# RILey-PCB_V2_0_v57.net
KiCad netlist of a schematic drawn in EAGLE
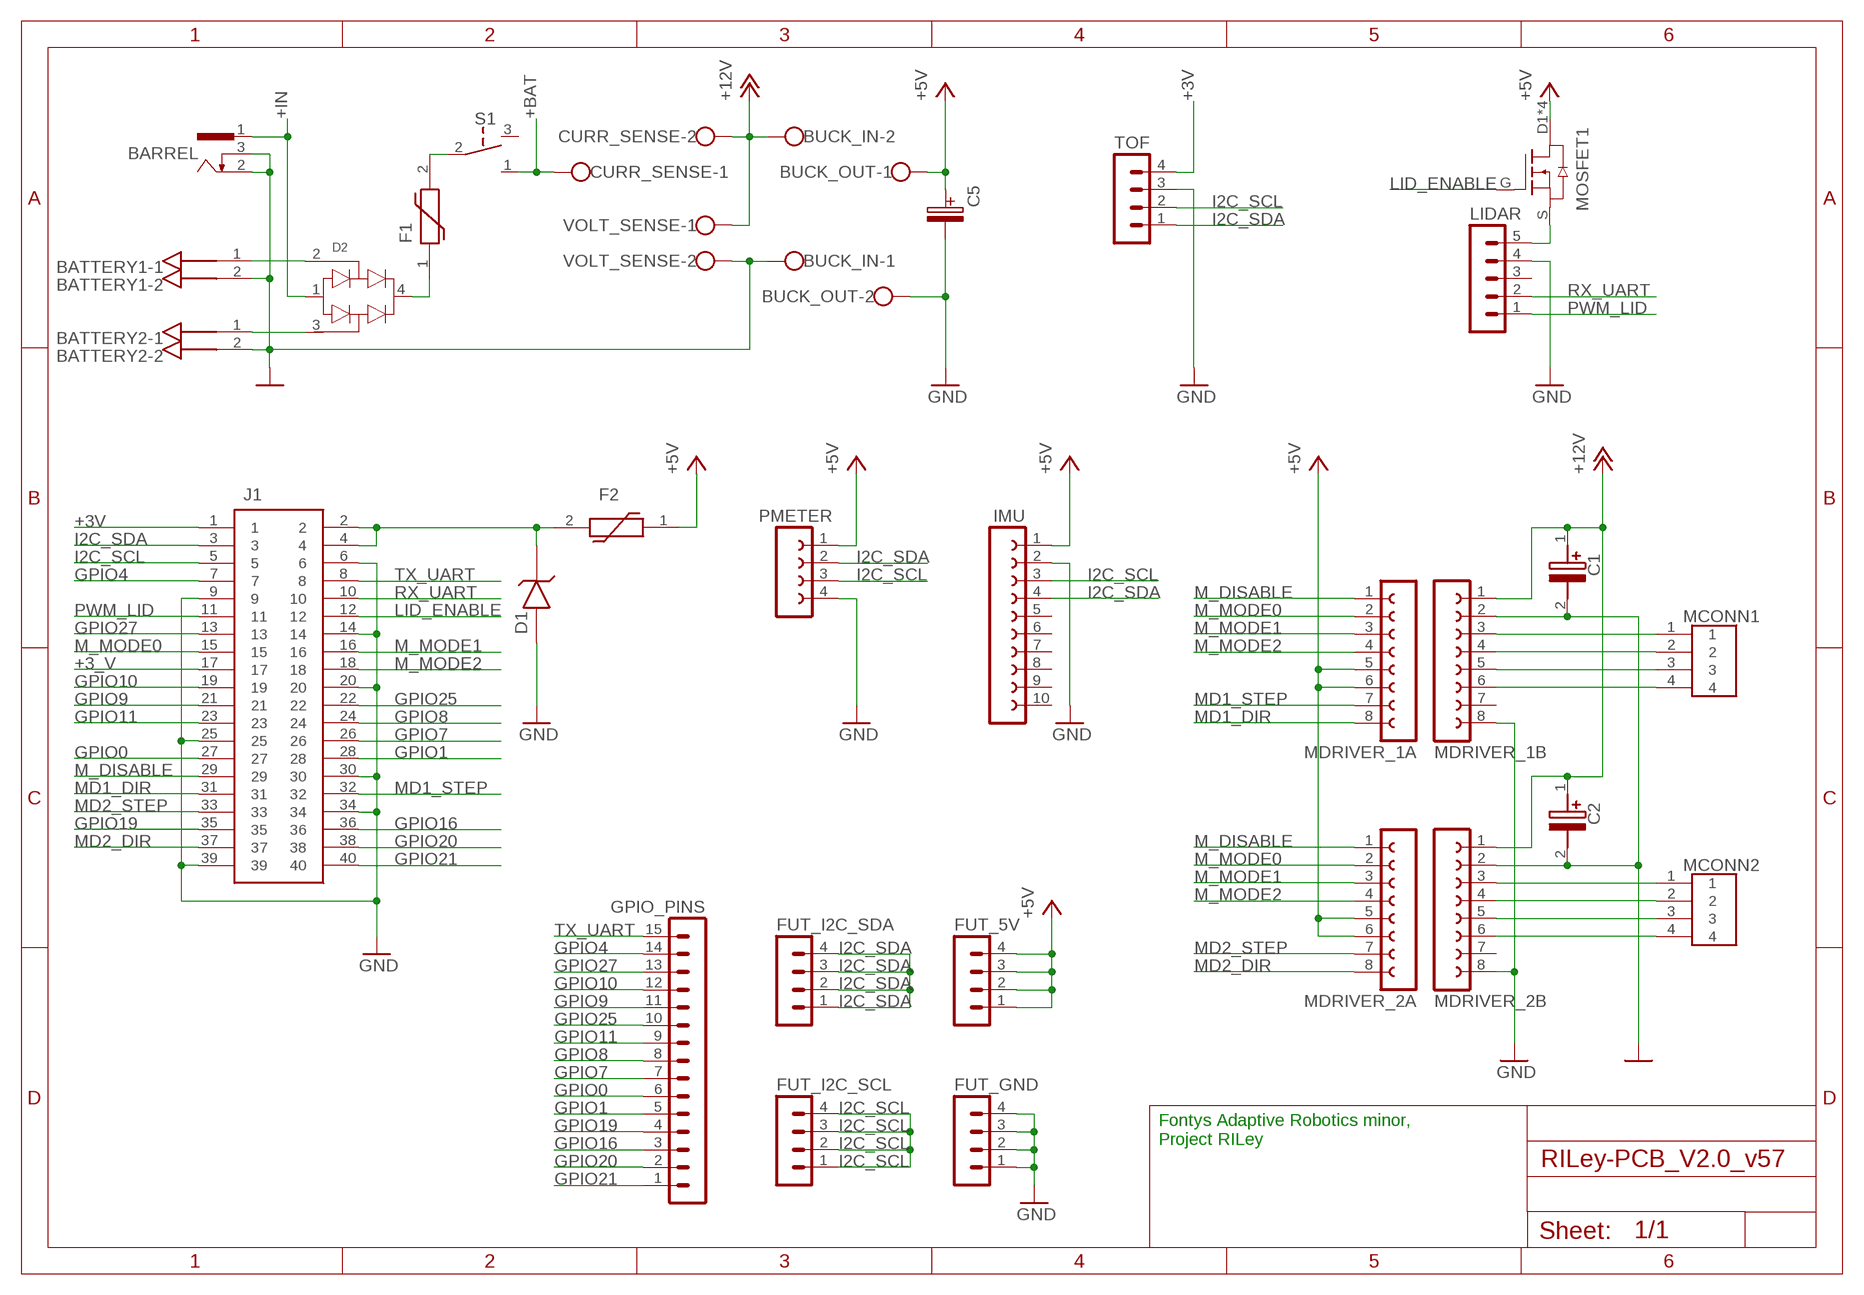
[diagram p0: schematic, sheet 1]

(export (version "E")
  (design (tool "Eeschema 10.0.6"))
  (components
    (comp (ref "BARREL")
      (value "DC_BARREL0-62")
      (footprint "eagle-import:733980-62")
      (libsource (lib "eagle-import") (part "DC_BARREL0-62"))
    )
    (comp (ref "BATTERY1")
      (value "0026604020")
      (footprint "eagle-import:KK41791-4020_2-PIN")
      (fields (field (name "MANUFACTURER") "Molex Inc"))
      (libsource (lib "eagle-import") (part "0026604020"))
    )
    (comp (ref "BATTERY2")
      (value "0026604020")
      (footprint "eagle-import:KK41791-4020_2-PIN")
      (fields (field (name "MANUFACTURER") "Molex Inc"))
      (libsource (lib "eagle-import") (part "0026604020"))
    )
    (comp (ref "BUCK_IN")
      (value "W237-102")
      (footprint "eagle-import:W237-102")
      (fields (field (name "MPN") "237-102"))
      (libsource (lib "eagle-import") (part "W237-102"))
    )
    (comp (ref "BUCK_OUT")
      (value "W237-102")
      (footprint "eagle-import:W237-102")
      (fields (field (name "MPN") "237-102"))
      (libsource (lib "eagle-import") (part "W237-102"))
    )
    (comp (ref "C1")
      (value "100uF")
      (footprint "eagle-import:CAPPRD250W50D655H1250")
      (fields
        (field (name "MANUFACTURER_PART_NUMBER") "UPS1E101MED")
        (field (name "RS_PART_NUMBER") "5194059P")
      )
      (libsource (lib "eagle-import") (part "UPS1E101MED"))
    )
    (comp (ref "C2")
      (value "100uF")
      (footprint "eagle-import:CAPPRD250W50D655H1250")
      (fields
        (field (name "MANUFACTURER_PART_NUMBER") "UPS1E101MED")
        (field (name "RS_PART_NUMBER") "5194059P")
      )
      (libsource (lib "eagle-import") (part "UPS1E101MED"))
    )
    (comp (ref "C5")
      (value "ELECTROLYTIC_CAPACITOR'8*20'")
      (footprint "eagle-import:ELECTROLYTIC_CAPACITOR")
      (libsource (lib "eagle-import") (part "ELECTROLYTIC_CAPACITOR'820'"))
    )
    (comp (ref "CURR_SENSE")
      (value "W237-102")
      (footprint "eagle-import:W237-102")
      (fields (field (name "MPN") "237-102"))
      (libsource (lib "eagle-import") (part "W237-102"))
    )
    (comp (ref "D1")
      (value "ZENER-THDO-35")
      (footprint "eagle-import:ZENER-TH")
      (libsource (lib "eagle-import") (part "ZENER-THDO-35"))
    )
    (comp (ref "D2")
      (value "DIODE-BRIGDE")
      (footprint "eagle-import:DIODE-BRIDGE")
      (libsource (lib "eagle-import") (part "DIODE-BRIGDE"))
    )
    (comp (ref "F1")
      (value "2920L400/15MR")
      (footprint "eagle-import:2920L400_15MR")
      (libsource (lib "eagle-import") (part "2920L400/15MR"))
    )
    (comp (ref "F2")
      (value "1812L300MR")
      (footprint "eagle-import:1812L300MR")
      (libsource (lib "eagle-import") (part "1812L300MR"))
    )
    (comp (ref "FUT_5V")
      (value "MA04-1_SMALLPAD")
      (footprint "eagle-import:MA04-1_S")
      (libsource (lib "eagle-import") (part "MA04-1_SMALLPAD"))
    )
    (comp (ref "FUT_GND")
      (value "MA04-1_SMALLPAD")
      (footprint "eagle-import:MA04-1_S")
      (libsource (lib "eagle-import") (part "MA04-1_SMALLPAD"))
    )
    (comp (ref "FUT_I2C_SCL")
      (value "MA04-1_SMALLPAD")
      (footprint "eagle-import:MA04-1_S")
      (libsource (lib "eagle-import") (part "MA04-1_SMALLPAD"))
    )
    (comp (ref "FUT_I2C_SDA")
      (value "MA04-1_SMALLPAD")
      (footprint "eagle-import:MA04-1_S")
      (libsource (lib "eagle-import") (part "MA04-1_SMALLPAD"))
    )
    (comp (ref "GPIO_PINS")
      (value "MA15-1W")
      (footprint "eagle-import:MA15-1W")
      (libsource (lib "eagle-import") (part "MA15-1W"))
    )
    (comp (ref "IMU")
      (value "FE10-1_3D")
      (footprint "eagle-import:FE10-1")
      (libsource (lib "eagle-import") (part "FE10-1_3D"))
    )
    (comp (ref "J1")
      (value "MC-254-40-00-ST-DIP")
      (footprint "eagle-import:MC-254-40-00-ST-DIP")
      (libsource (lib "eagle-import") (part "MC-254-40-00-ST-DIP"))
    )
    (comp (ref "LIDAR")
      (value "MA05-1_SMALLPAD")
      (footprint "eagle-import:MA05-1_S")
      (libsource (lib "eagle-import") (part "MA05-1_SMALLPAD"))
    )
    (comp (ref "MCONN1")
      (value "B4B-XH-A_LF__SN_")
      (footprint "eagle-import:B4B-XH-A_LF__SN_")
      (fields (field (name "MANUFACTURER_PART_NUMBER") "B4B-XH-A(LF)(SN)"))
      (libsource (lib "eagle-import") (part "B4B-XH-A_LF__SN_"))
    )
    (comp (ref "MCONN2")
      (value "B4B-XH-A_LF__SN_")
      (footprint "eagle-import:B4B-XH-A_LF__SN_")
      (fields (field (name "MANUFACTURER_PART_NUMBER") "B4B-XH-A(LF)(SN)"))
      (libsource (lib "eagle-import") (part "B4B-XH-A_LF__SN_"))
    )
    (comp (ref "MDRIVER_1A")
      (value "FE08-1_3D")
      (footprint "eagle-import:FE08-1")
      (libsource (lib "eagle-import") (part "FE08-1_3D"))
    )
    (comp (ref "MDRIVER_1B")
      (value "FE08-1_3D")
      (footprint "eagle-import:FE08-1")
      (libsource (lib "eagle-import") (part "FE08-1_3D"))
    )
    (comp (ref "MDRIVER_2A")
      (value "FE08-1_3D")
      (footprint "eagle-import:FE08-1")
      (libsource (lib "eagle-import") (part "FE08-1_3D"))
    )
    (comp (ref "MDRIVER_2B")
      (value "FE08-1_3D")
      (footprint "eagle-import:FE08-1")
      (libsource (lib "eagle-import") (part "FE08-1_3D"))
    )
    (comp (ref "MOSFET1")
      (value "SI2303CDS-T1-GE3")
      (footprint "eagle-import:TSOP6_SOT457")
      (libsource (lib "eagle-import") (part "PMN30UNH"))
    )
    (comp (ref "PMETER")
      (value "FE04-1")
      (footprint "eagle-import:FE04-1")
      (libsource (lib "eagle-import") (part "FE04-1"))
    )
    (comp (ref "S1")
      (value "1101M2S3CQE2")
      (footprint "eagle-import:1000-SERIES(SPDT)")
      (fields (field (name "RS_PART_NUMBER") "1617340"))
      (libsource (lib "eagle-import") (part "1101M2S3CQE2"))
    )
    (comp (ref "TOF")
      (value "MA04-1W")
      (footprint "eagle-import:MA04-1W")
      (libsource (lib "eagle-import") (part "MA04-1W"))
    )
    (comp (ref "VOLT_SENSE")
      (value "W237-102")
      (footprint "eagle-import:W237-102")
      (fields (field (name "MPN") "237-102"))
      (libsource (lib "eagle-import") (part "W237-102"))
    )
  )
  (nets
    (net (code "1") (name "+5V") (class "Default")
      (node (ref "BUCK_OUT") (pin "1") (pinfunction "KL_1") (pintype "passive"))
      (node (ref "C5") (pin "+") (pinfunction "+_+") (pintype "bidirectional"))
      (node (ref "F2") (pin "1") (pinfunction "1_1") (pintype "bidirectional"))
      (node (ref "FUT_5V") (pin "1") (pinfunction "1_1") (pintype "passive"))
      (node (ref "FUT_5V") (pin "2") (pinfunction "2_2") (pintype "passive"))
      (node (ref "FUT_5V") (pin "3") (pinfunction "3_3") (pintype "passive"))
      (node (ref "FUT_5V") (pin "4") (pinfunction "4_4") (pintype "passive"))
      (node (ref "IMU") (pin "1") (pinfunction "1_1") (pintype "passive"))
      (node (ref "MDRIVER_1A") (pin "5") (pinfunction "5_5") (pintype "passive"))
      (node (ref "MDRIVER_1A") (pin "6") (pinfunction "6_6") (pintype "passive"))
      (node (ref "MDRIVER_2A") (pin "5") (pinfunction "5_5") (pintype "passive"))
      (node (ref "MDRIVER_2A") (pin "6") (pinfunction "6_6") (pintype "passive"))
      (node (ref "MOSFET1") (pin "D1") (pinfunction "D_D1") (pintype "bidirectional"))
      (node (ref "MOSFET1") (pin "D2") (pinfunction "D_D2") (pintype "bidirectional"))
      (node (ref "MOSFET1") (pin "D3") (pinfunction "D_D3") (pintype "bidirectional"))
      (node (ref "MOSFET1") (pin "D4") (pinfunction "D_D4") (pintype "bidirectional"))
      (node (ref "PMETER") (pin "1") (pinfunction "1_1") (pintype "passive"))
    )
    (net (code "2") (name "+12V") (class "Default")
      (node (ref "BUCK_IN") (pin "2") (pinfunction "KL_2") (pintype "passive"))
      (node (ref "C1") (pin "1") (pinfunction "+_1") (pintype "bidirectional"))
      (node (ref "C2") (pin "1") (pinfunction "+_1") (pintype "bidirectional"))
      (node (ref "CURR_SENSE") (pin "2") (pinfunction "KL_2") (pintype "passive"))
      (node (ref "MDRIVER_1B") (pin "1") (pinfunction "1_1") (pintype "passive"))
      (node (ref "MDRIVER_2B") (pin "1") (pinfunction "1_1") (pintype "passive"))
      (node (ref "VOLT_SENSE") (pin "1") (pinfunction "KL_1") (pintype "passive"))
    )
    (net (code "3") (name "/+3V") (class "Default")
      (node (ref "J1") (pin "1") (pinfunction "1_1") (pintype "bidirectional"))
      (node (ref "TOF") (pin "4") (pinfunction "4_4") (pintype "passive"))
    )
    (net (code "4") (name "/+3_V") (class "Default")
      (node (ref "J1") (pin "17") (pinfunction "17_17") (pintype "bidirectional"))
    )
    (net (code "5") (name "/+BAT") (class "Default")
      (node (ref "CURR_SENSE") (pin "1") (pinfunction "KL_1") (pintype "passive"))
      (node (ref "S1") (pin "1") (pinfunction "1_1") (pintype "bidirectional"))
    )
    (net (code "6") (name "/+IN") (class "Default")
      (node (ref "BARREL") (pin "1") (pinfunction "1_1") (pintype "passive"))
      (node (ref "D2") (pin "1") (pinfunction "1_1") (pintype "input"))
    )
    (net (code "7") (name "/GPIO0") (class "Default")
      (node (ref "GPIO_PINS") (pin "6") (pinfunction "6_6") (pintype "passive"))
      (node (ref "J1") (pin "27") (pinfunction "27_27") (pintype "bidirectional"))
    )
    (net (code "8") (name "/GPIO1") (class "Default")
      (node (ref "GPIO_PINS") (pin "5") (pinfunction "5_5") (pintype "passive"))
      (node (ref "J1") (pin "28") (pinfunction "28_28") (pintype "bidirectional"))
    )
    (net (code "9") (name "/GPIO4") (class "Default")
      (node (ref "GPIO_PINS") (pin "14") (pinfunction "14_14") (pintype "passive"))
      (node (ref "J1") (pin "7") (pinfunction "7_7") (pintype "bidirectional"))
    )
    (net (code "10") (name "/GPIO7") (class "Default")
      (node (ref "GPIO_PINS") (pin "7") (pinfunction "7_7") (pintype "passive"))
      (node (ref "J1") (pin "26") (pinfunction "26_26") (pintype "bidirectional"))
    )
    (net (code "11") (name "/GPIO8") (class "Default")
      (node (ref "GPIO_PINS") (pin "8") (pinfunction "8_8") (pintype "passive"))
      (node (ref "J1") (pin "24") (pinfunction "24_24") (pintype "bidirectional"))
    )
    (net (code "12") (name "/GPIO9") (class "Default")
      (node (ref "GPIO_PINS") (pin "11") (pinfunction "11_11") (pintype "passive"))
      (node (ref "J1") (pin "21") (pinfunction "21_21") (pintype "bidirectional"))
    )
    (net (code "13") (name "/GPIO10") (class "Default")
      (node (ref "GPIO_PINS") (pin "12") (pinfunction "12_12") (pintype "passive"))
      (node (ref "J1") (pin "19") (pinfunction "19_19") (pintype "bidirectional"))
    )
    (net (code "14") (name "/GPIO11") (class "Default")
      (node (ref "GPIO_PINS") (pin "9") (pinfunction "9_9") (pintype "passive"))
      (node (ref "J1") (pin "23") (pinfunction "23_23") (pintype "bidirectional"))
    )
    (net (code "15") (name "/GPIO16") (class "Default")
      (node (ref "GPIO_PINS") (pin "3") (pinfunction "3_3") (pintype "passive"))
      (node (ref "J1") (pin "36") (pinfunction "36_36") (pintype "bidirectional"))
    )
    (net (code "16") (name "/GPIO19") (class "Default")
      (node (ref "GPIO_PINS") (pin "4") (pinfunction "4_4") (pintype "passive"))
      (node (ref "J1") (pin "35") (pinfunction "35_35") (pintype "bidirectional"))
    )
    (net (code "17") (name "/GPIO20") (class "Default")
      (node (ref "GPIO_PINS") (pin "2") (pinfunction "2_2") (pintype "passive"))
      (node (ref "J1") (pin "38") (pinfunction "38_38") (pintype "bidirectional"))
    )
    (net (code "18") (name "/GPIO21") (class "Default")
      (node (ref "GPIO_PINS") (pin "1") (pinfunction "1_1") (pintype "passive"))
      (node (ref "J1") (pin "40") (pinfunction "40_40") (pintype "bidirectional"))
    )
    (net (code "19") (name "/GPIO25") (class "Default")
      (node (ref "GPIO_PINS") (pin "10") (pinfunction "10_10") (pintype "passive"))
      (node (ref "J1") (pin "22") (pinfunction "22_22") (pintype "bidirectional"))
    )
    (net (code "20") (name "/GPIO27") (class "Default")
      (node (ref "GPIO_PINS") (pin "13") (pinfunction "13_13") (pintype "passive"))
      (node (ref "J1") (pin "13") (pinfunction "13_13") (pintype "bidirectional"))
    )
    (net (code "21") (name "/I2C_SCL") (class "Default")
      (node (ref "FUT_I2C_SCL") (pin "1") (pinfunction "1_1") (pintype "passive"))
      (node (ref "FUT_I2C_SCL") (pin "2") (pinfunction "2_2") (pintype "passive"))
      (node (ref "FUT_I2C_SCL") (pin "3") (pinfunction "3_3") (pintype "passive"))
      (node (ref "FUT_I2C_SCL") (pin "4") (pinfunction "4_4") (pintype "passive"))
      (node (ref "IMU") (pin "3") (pinfunction "3_3") (pintype "passive"))
      (node (ref "J1") (pin "5") (pinfunction "5_5") (pintype "bidirectional"))
      (node (ref "PMETER") (pin "3") (pinfunction "3_3") (pintype "passive"))
      (node (ref "TOF") (pin "2") (pinfunction "2_2") (pintype "passive"))
    )
    (net (code "22") (name "/I2C_SDA") (class "Default")
      (node (ref "FUT_I2C_SDA") (pin "1") (pinfunction "1_1") (pintype "passive"))
      (node (ref "FUT_I2C_SDA") (pin "2") (pinfunction "2_2") (pintype "passive"))
      (node (ref "FUT_I2C_SDA") (pin "3") (pinfunction "3_3") (pintype "passive"))
      (node (ref "FUT_I2C_SDA") (pin "4") (pinfunction "4_4") (pintype "passive"))
      (node (ref "IMU") (pin "4") (pinfunction "4_4") (pintype "passive"))
      (node (ref "J1") (pin "3") (pinfunction "3_3") (pintype "bidirectional"))
      (node (ref "PMETER") (pin "2") (pinfunction "2_2") (pintype "passive"))
      (node (ref "TOF") (pin "1") (pinfunction "1_1") (pintype "passive"))
    )
    (net (code "23") (name "/LID_ENABLE") (class "Default")
      (node (ref "J1") (pin "12") (pinfunction "12_12") (pintype "bidirectional"))
      (node (ref "MOSFET1") (pin "G") (pinfunction "G_G") (pintype "bidirectional"))
    )
    (net (code "24") (name "/MD1_DIR") (class "Default")
      (node (ref "J1") (pin "31") (pinfunction "31_31") (pintype "bidirectional"))
      (node (ref "MDRIVER_1A") (pin "8") (pinfunction "8_8") (pintype "passive"))
    )
    (net (code "25") (name "/MD1_STEP") (class "Default")
      (node (ref "J1") (pin "32") (pinfunction "32_32") (pintype "bidirectional"))
      (node (ref "MDRIVER_1A") (pin "7") (pinfunction "7_7") (pintype "passive"))
    )
    (net (code "26") (name "/MD2_DIR") (class "Default")
      (node (ref "J1") (pin "37") (pinfunction "37_37") (pintype "bidirectional"))
      (node (ref "MDRIVER_2A") (pin "8") (pinfunction "8_8") (pintype "passive"))
    )
    (net (code "27") (name "/MD2_STEP") (class "Default")
      (node (ref "J1") (pin "33") (pinfunction "33_33") (pintype "bidirectional"))
      (node (ref "MDRIVER_2A") (pin "7") (pinfunction "7_7") (pintype "passive"))
    )
    (net (code "28") (name "/M_DISABLE") (class "Default")
      (node (ref "J1") (pin "29") (pinfunction "29_29") (pintype "bidirectional"))
      (node (ref "MDRIVER_1A") (pin "1") (pinfunction "1_1") (pintype "passive"))
      (node (ref "MDRIVER_2A") (pin "1") (pinfunction "1_1") (pintype "passive"))
    )
    (net (code "29") (name "/M_MODE0") (class "Default")
      (node (ref "J1") (pin "15") (pinfunction "15_15") (pintype "bidirectional"))
      (node (ref "MDRIVER_1A") (pin "2") (pinfunction "2_2") (pintype "passive"))
      (node (ref "MDRIVER_2A") (pin "2") (pinfunction "2_2") (pintype "passive"))
    )
    (net (code "30") (name "/M_MODE1") (class "Default")
      (node (ref "J1") (pin "16") (pinfunction "16_16") (pintype "bidirectional"))
      (node (ref "MDRIVER_1A") (pin "3") (pinfunction "3_3") (pintype "passive"))
      (node (ref "MDRIVER_2A") (pin "3") (pinfunction "3_3") (pintype "passive"))
    )
    (net (code "31") (name "/M_MODE2") (class "Default")
      (node (ref "J1") (pin "18") (pinfunction "18_18") (pintype "bidirectional"))
      (node (ref "MDRIVER_1A") (pin "4") (pinfunction "4_4") (pintype "passive"))
      (node (ref "MDRIVER_2A") (pin "4") (pinfunction "4_4") (pintype "passive"))
    )
    (net (code "32") (name "/PWM_LID") (class "Default")
      (node (ref "J1") (pin "11") (pinfunction "11_11") (pintype "bidirectional"))
      (node (ref "LIDAR") (pin "1") (pinfunction "1_1") (pintype "passive"))
    )
    (net (code "33") (name "/RX_UART") (class "Default")
      (node (ref "J1") (pin "10") (pinfunction "10_10") (pintype "bidirectional"))
      (node (ref "LIDAR") (pin "2") (pinfunction "2_2") (pintype "passive"))
    )
    (net (code "34") (name "/TX_UART") (class "Default")
      (node (ref "GPIO_PINS") (pin "15") (pinfunction "15_15") (pintype "passive"))
      (node (ref "J1") (pin "8") (pinfunction "8_8") (pintype "bidirectional"))
    )
    (net (code "35") (name "0V") (class "Default")
      (node (ref "BARREL") (pin "2") (pinfunction "2_2") (pintype "passive"))
      (node (ref "BARREL") (pin "3") (pinfunction "3_3") (pintype "passive"))
      (node (ref "BATTERY1") (pin "2") (pinfunction "P$1_2") (pintype "bidirectional"))
      (node (ref "BATTERY2") (pin "2") (pinfunction "P$1_2") (pintype "bidirectional"))
      (node (ref "BUCK_IN") (pin "1") (pinfunction "KL_1") (pintype "passive"))
      (node (ref "C1") (pin "2") (pinfunction "-_2") (pintype "bidirectional"))
      (node (ref "C2") (pin "2") (pinfunction "-_2") (pintype "bidirectional"))
      (node (ref "MDRIVER_1B") (pin "2") (pinfunction "2_2") (pintype "passive"))
      (node (ref "MDRIVER_2B") (pin "2") (pinfunction "2_2") (pintype "passive"))
      (node (ref "VOLT_SENSE") (pin "2") (pinfunction "KL_2") (pintype "passive"))
    )
    (net (code "36") (name "GND") (class "Default")
      (node (ref "BUCK_OUT") (pin "2") (pinfunction "KL_2") (pintype "passive"))
      (node (ref "C5") (pin "-") (pinfunction "-_-") (pintype "bidirectional"))
      (node (ref "D1") (pin "A") (pinfunction "A_A") (pintype "bidirectional"))
      (node (ref "FUT_GND") (pin "1") (pinfunction "1_1") (pintype "passive"))
      (node (ref "FUT_GND") (pin "2") (pinfunction "2_2") (pintype "passive"))
      (node (ref "FUT_GND") (pin "3") (pinfunction "3_3") (pintype "passive"))
      (node (ref "FUT_GND") (pin "4") (pinfunction "4_4") (pintype "passive"))
      (node (ref "IMU") (pin "2") (pinfunction "2_2") (pintype "passive"))
      (node (ref "J1") (pin "14") (pinfunction "14_14") (pintype "bidirectional"))
      (node (ref "J1") (pin "20") (pinfunction "20_20") (pintype "bidirectional"))
      (node (ref "J1") (pin "25") (pinfunction "25_25") (pintype "bidirectional"))
      (node (ref "J1") (pin "30") (pinfunction "30_30") (pintype "bidirectional"))
      (node (ref "J1") (pin "34") (pinfunction "34_34") (pintype "bidirectional"))
      (node (ref "J1") (pin "39") (pinfunction "39_39") (pintype "bidirectional"))
      (node (ref "J1") (pin "6") (pinfunction "6_6") (pintype "bidirectional"))
      (node (ref "J1") (pin "9") (pinfunction "9_9") (pintype "bidirectional"))
      (node (ref "LIDAR") (pin "4") (pinfunction "4_4") (pintype "passive"))
      (node (ref "MDRIVER_1B") (pin "8") (pinfunction "8_8") (pintype "passive"))
      (node (ref "MDRIVER_2B") (pin "8") (pinfunction "8_8") (pintype "passive"))
      (node (ref "PMETER") (pin "4") (pinfunction "4_4") (pintype "passive"))
      (node (ref "TOF") (pin "3") (pinfunction "3_3") (pintype "passive"))
    )
    (net (code "37") (name "Net-(BATTERY1A-P$1)") (class "Default")
      (node (ref "BATTERY1") (pin "1") (pinfunction "P$1_1") (pintype "bidirectional"))
      (node (ref "D2") (pin "2") (pinfunction "2_2") (pintype "bidirectional"))
    )
    (net (code "38") (name "Net-(BATTERY2A-P$1)") (class "Default")
      (node (ref "BATTERY2") (pin "1") (pinfunction "P$1_1") (pintype "bidirectional"))
      (node (ref "D2") (pin "3") (pinfunction "3_3") (pintype "bidirectional"))
    )
    (net (code "39") (name "Net-(D1-PadC)") (class "Default")
      (node (ref "D1") (pin "C") (pinfunction "C_C") (pintype "bidirectional"))
      (node (ref "F2") (pin "2") (pinfunction "2_2") (pintype "bidirectional"))
      (node (ref "J1") (pin "2") (pinfunction "2_2") (pintype "bidirectional"))
      (node (ref "J1") (pin "4") (pinfunction "4_4") (pintype "bidirectional"))
    )
    (net (code "40") (name "Net-(D2-Pad4)") (class "Default")
      (node (ref "D2") (pin "4") (pinfunction "4_4") (pintype "output"))
      (node (ref "F1") (pin "1") (pinfunction "1_1") (pintype "bidirectional"))
    )
    (net (code "41") (name "Net-(F1-Pad2)") (class "Default")
      (node (ref "F1") (pin "2") (pinfunction "2_2") (pintype "bidirectional"))
      (node (ref "S1") (pin "2") (pinfunction "2_2") (pintype "bidirectional"))
    )
    (net (code "42") (name "Net-(LIDAR-Pad5)") (class "Default")
      (node (ref "LIDAR") (pin "5") (pinfunction "5_5") (pintype "passive"))
      (node (ref "MOSFET1") (pin "S") (pinfunction "S_S") (pintype "bidirectional"))
    )
    (net (code "43") (name "Net-(MCONN1-Pad1)") (class "Default")
      (node (ref "MCONN1") (pin "1") (pinfunction "1_1") (pintype "bidirectional"))
      (node (ref "MDRIVER_1B") (pin "3") (pinfunction "3_3") (pintype "passive"))
    )
    (net (code "44") (name "Net-(MCONN1-Pad2)") (class "Default")
      (node (ref "MCONN1") (pin "2") (pinfunction "2_2") (pintype "bidirectional"))
      (node (ref "MDRIVER_1B") (pin "4") (pinfunction "4_4") (pintype "passive"))
    )
    (net (code "45") (name "Net-(MCONN1-Pad3)") (class "Default")
      (node (ref "MCONN1") (pin "3") (pinfunction "3_3") (pintype "bidirectional"))
      (node (ref "MDRIVER_1B") (pin "5") (pinfunction "5_5") (pintype "passive"))
    )
    (net (code "46") (name "Net-(MCONN1-Pad4)") (class "Default")
      (node (ref "MCONN1") (pin "4") (pinfunction "4_4") (pintype "bidirectional"))
      (node (ref "MDRIVER_1B") (pin "6") (pinfunction "6_6") (pintype "passive"))
    )
    (net (code "47") (name "Net-(MCONN2-Pad1)") (class "Default")
      (node (ref "MCONN2") (pin "1") (pinfunction "1_1") (pintype "bidirectional"))
      (node (ref "MDRIVER_2B") (pin "3") (pinfunction "3_3") (pintype "passive"))
    )
    (net (code "48") (name "Net-(MCONN2-Pad2)") (class "Default")
      (node (ref "MCONN2") (pin "2") (pinfunction "2_2") (pintype "bidirectional"))
      (node (ref "MDRIVER_2B") (pin "4") (pinfunction "4_4") (pintype "passive"))
    )
    (net (code "49") (name "Net-(MCONN2-Pad3)") (class "Default")
      (node (ref "MCONN2") (pin "3") (pinfunction "3_3") (pintype "bidirectional"))
      (node (ref "MDRIVER_2B") (pin "5") (pinfunction "5_5") (pintype "passive"))
    )
    (net (code "50") (name "Net-(MCONN2-Pad4)") (class "Default")
      (node (ref "MCONN2") (pin "4") (pinfunction "4_4") (pintype "bidirectional"))
      (node (ref "MDRIVER_2B") (pin "6") (pinfunction "6_6") (pintype "passive"))
    )
    (net (code "51") (name "unconnected-(IMU-Pad5)") (class "Default")
      (node (ref "IMU") (pin "5") (pinfunction "5_5") (pintype "passive"))
    )
    (net (code "52") (name "unconnected-(IMU-Pad6)") (class "Default")
      (node (ref "IMU") (pin "6") (pinfunction "6_6") (pintype "passive"))
    )
    (net (code "53") (name "unconnected-(IMU-Pad7)") (class "Default")
      (node (ref "IMU") (pin "7") (pinfunction "7_7") (pintype "passive"))
    )
    (net (code "54") (name "unconnected-(IMU-Pad8)") (class "Default")
      (node (ref "IMU") (pin "8") (pinfunction "8_8") (pintype "passive"))
    )
    (net (code "55") (name "unconnected-(IMU-Pad9)") (class "Default")
      (node (ref "IMU") (pin "9") (pinfunction "9_9") (pintype "passive"))
    )
    (net (code "56") (name "unconnected-(IMU-Pad10)") (class "Default")
      (node (ref "IMU") (pin "10") (pinfunction "10_10") (pintype "passive"))
    )
    (net (code "57") (name "unconnected-(LIDAR-Pad3)") (class "Default")
      (node (ref "LIDAR") (pin "3") (pinfunction "3_3") (pintype "passive"))
    )
    (net (code "58") (name "unconnected-(MDRIVER_1B-Pad7)") (class "Default")
      (node (ref "MDRIVER_1B") (pin "7") (pinfunction "7_7") (pintype "passive"))
    )
    (net (code "59") (name "unconnected-(MDRIVER_2B-Pad7)") (class "Default")
      (node (ref "MDRIVER_2B") (pin "7") (pinfunction "7_7") (pintype "passive"))
    )
    (net (code "60") (name "unconnected-(S1-Pad3)") (class "Default")
      (node (ref "S1") (pin "3") (pinfunction "3_3") (pintype "bidirectional"))
    )
  )
)
